# PressSensor2.net
KiCad netlist of a schematic drawn in Altium Designer
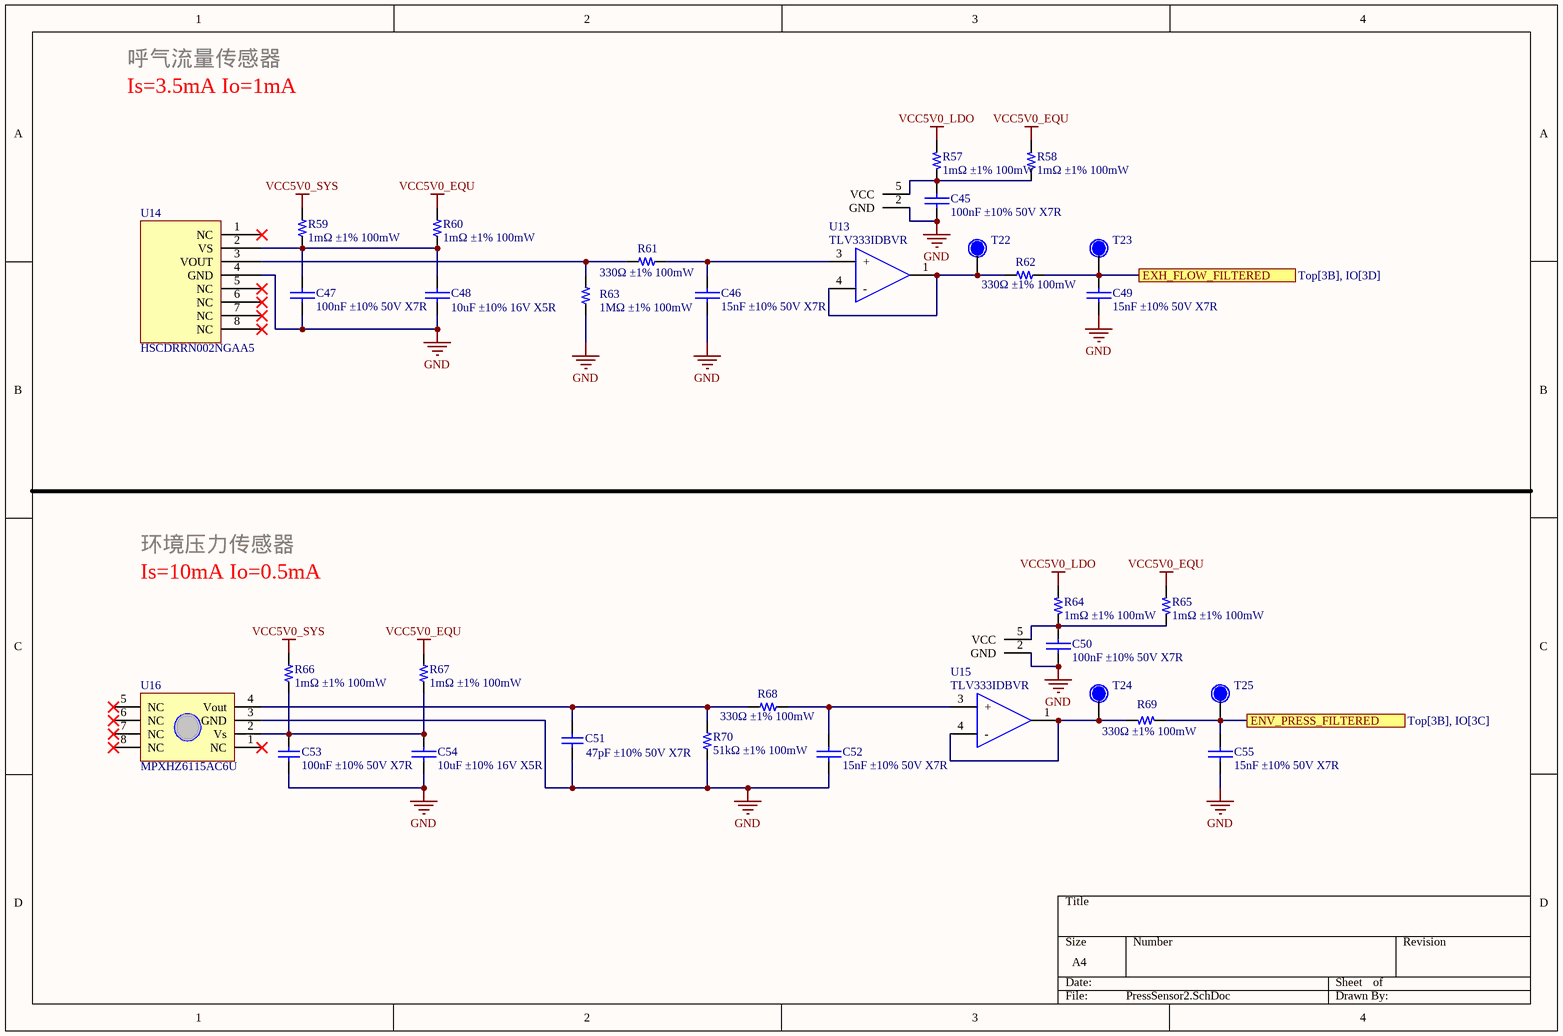
[diagram p0: PressSensor2.SchDoc]

(export (version "E")
  (design (tool "Eeschema 10.0.6"))
  (components
    (comp (ref "C45") (value "100nF ±10% 50V X7R") (footprint "C-0603") (libsource (lib "*") (part "CAP")))
    (comp (ref "C46")
      (value "15nF ±10% 50V X7R")
      (footprint "C-0603")
      (description "Capacitor")
      (libsource (lib "*") (part "CAP"))
    )
    (comp (ref "C47") (value "100nF ±10% 50V X7R") (footprint "C-0603") (libsource (lib "*") (part "CAP")))
    (comp (ref "C48")
      (value "10uF ±10% 16V X5R")
      (footprint "C-0805")
      (description "Capacitor")
      (libsource (lib "*") (part "CAP"))
    )
    (comp (ref "C49")
      (value "15nF ±10% 50V X7R")
      (footprint "C-0603")
      (description "Capacitor")
      (libsource (lib "*") (part "CAP"))
    )
    (comp (ref "C50") (value "100nF ±10% 50V X7R") (footprint "C-0603") (libsource (lib "*") (part "CAP")))
    (comp (ref "C51")
      (value "47pF ±10% 50V X7R")
      (footprint "C-0603")
      (description "贴片瓷介电容100nF±5%,0805")
      (libsource (lib "电容") (part "100nF_1"))
    )
    (comp (ref "C52")
      (value "15nF ±10% 50V X7R")
      (footprint "C-0603")
      (description "Capacitor")
      (libsource (lib "*") (part "CAP"))
    )
    (comp (ref "C53")
      (value "100nF ±10% 50V X7R")
      (footprint "C-0603")
      (libsource (lib "电容") (part "100nF_1"))
    )
    (comp (ref "C54")
      (value "10uF ±10% 16V X5R")
      (footprint "C-0805")
      (description "Capacitor")
      (libsource (lib "*") (part "CAP"))
    )
    (comp (ref "C55")
      (value "15nF ±10% 50V X7R")
      (footprint "C-0603")
      (description "Capacitor")
      (libsource (lib "*") (part "CAP"))
    )
    (comp (ref "R57")
      (value "1mΩ ±1% 100mW")
      (footprint "R-0603")
      (description "国巨\r\n1mΩ ±1% 100mW")
      (libsource (lib "电阻") (part "10K_1"))
    )
    (comp (ref "R58")
      (value "1mΩ ±1% 100mW")
      (footprint "R-0603")
      (description "国巨\r\n1mΩ ±1% 100mW")
      (libsource (lib "电阻") (part "10K_1"))
    )
    (comp (ref "R59")
      (value "1mΩ ±1% 100mW")
      (footprint "R-0603")
      (description "国巨\r\n1mΩ ±1% 100mW")
      (libsource (lib "Device") (part "R-0603"))
    )
    (comp (ref "R60")
      (value "1mΩ ±1% 100mW")
      (footprint "R-0603")
      (description "国巨\r\n1mΩ ±1% 100mW")
      (libsource (lib "Device") (part "R-0603"))
    )
    (comp (ref "R61")
      (value "330Ω ±1% 100mW")
      (footprint "R-0603")
      (libsource (lib "Device") (part "R-0603"))
    )
    (comp (ref "R62")
      (value "330Ω ±1% 100mW")
      (footprint "R-0603")
      (libsource (lib "Device") (part "R-0603"))
    )
    (comp (ref "R63") (value "1MΩ ±1% 100mW") (footprint "R-0603") (libsource (lib "Device") (part "R-0603")))
    (comp (ref "R64")
      (value "1mΩ ±1% 100mW")
      (footprint "R-0603")
      (description "国巨\r\n1mΩ ±1% 100mW")
      (libsource (lib "电阻") (part "10K_1"))
    )
    (comp (ref "R65")
      (value "1mΩ ±1% 100mW")
      (footprint "R-0603")
      (description "国巨\r\n1mΩ ±1% 100mW")
      (libsource (lib "电阻") (part "10K_1"))
    )
    (comp (ref "R66")
      (value "1mΩ ±1% 100mW")
      (footprint "R-0603")
      (description "国巨\r\n1mΩ ±1% 100mW")
      (libsource (lib "Device") (part "R-0603"))
    )
    (comp (ref "R67")
      (value "1mΩ ±1% 100mW")
      (footprint "R-0603")
      (description "国巨\r\n1mΩ ±1% 100mW")
      (libsource (lib "Device") (part "R-0603"))
    )
    (comp (ref "R68")
      (value "330Ω ±1% 100mW")
      (footprint "R-0603")
      (libsource (lib "Device") (part "R-0603"))
    )
    (comp (ref "R69")
      (value "330Ω ±1% 100mW")
      (footprint "R-0603")
      (description "国巨RC0805FR-07100R")
      (libsource (lib "电阻") (part "100Ω_1"))
    )
    (comp (ref "R70")
      (value "51kΩ ±1% 100mW")
      (footprint "R-0603")
      (description "国巨RC0805FR-0710K")
      (libsource (lib "电阻") (part "10K_1"))
    )
    (comp (ref "T22")
      (value "Test?")
      (footprint "TestPad_SMD")
      (description "TestPad_SMD")
      (libsource (lib "Component") (part "TestPad_SMD"))
    )
    (comp (ref "T23")
      (value "Test?")
      (footprint "TestPad_SMD")
      (description "TestPad_SMD")
      (libsource (lib "Component") (part "TestPad_SMD"))
    )
    (comp (ref "T24")
      (value "Test?")
      (footprint "TestPad_SMD")
      (description "TestPad_SMD")
      (libsource (lib "Component") (part "TestPad_SMD"))
    )
    (comp (ref "T25")
      (value "Test?")
      (footprint "TestPad_SMD")
      (description "TestPad_SMD")
      (libsource (lib "Component") (part "TestPad_SMD"))
    )
    (comp (ref "U13")
      (value "TLV333IDBVR")
      (footprint "SOT23-5")
      (description "品牌：TI，型号：TLV333IDBVR,SOIC-8,–25°~+85°C,单运放，ROHS")
      (libsource (lib "IC") (part "TLV333IDBVR"))
    )
    (comp (ref "U14")
      (value "HSCDRRN002NGAA5")
      (footprint "SSCDRR")
      (libsource (lib "NBP电源板") (part "SSCMJJ010KDAA5"))
    )
    (comp (ref "U15")
      (value "TLV333IDBVR")
      (footprint "SOT23-5")
      (description "品牌：TI，型号：TLV333IDBVR,SOIC-8,–25°~+85°C,单运放，ROHS")
      (libsource (lib "IC") (part "TLV333IDBVR"))
    )
    (comp (ref "U16")
      (value "MPXHZ6115AC6U")
      (footprint "1317")
      (libsource (lib "余临时库") (part "MPXHZ6115AC6U"))
    )
  )
  (nets
    (net (code "1") (name "/ENV_PRESS_FILTERED") (class "Default")
      (node (ref "C55") (pin "2") (pinfunction "2_2") (pintype "passive"))
      (node (ref "R69") (pin "1") (pinfunction "TOP_1") (pintype "passive"))
      (node (ref "T25") (pin "1") (pinfunction "1_1") (pintype "passive"))
    )
    (net (code "2") (name "/EXH_FLOW_FILTERED") (class "Default")
      (node (ref "C49") (pin "2") (pinfunction "2_2") (pintype "passive"))
      (node (ref "R62") (pin "1") (pinfunction "1_1") (pintype "passive"))
      (node (ref "T23") (pin "1") (pinfunction "1_1") (pintype "passive"))
    )
    (net (code "3") (name "GND") (class "Default")
      (node (ref "C45") (pin "1") (pinfunction "1_1") (pintype "passive"))
      (node (ref "C46") (pin "1") (pinfunction "1_1") (pintype "passive"))
      (node (ref "C47") (pin "1") (pinfunction "1_1") (pintype "passive"))
      (node (ref "C48") (pin "1") (pinfunction "1_1") (pintype "passive"))
      (node (ref "C49") (pin "1") (pinfunction "1_1") (pintype "passive"))
      (node (ref "C50") (pin "2") (pinfunction "2_2") (pintype "passive"))
      (node (ref "C51") (pin "1") (pinfunction "1_1") (pintype "passive"))
      (node (ref "C52") (pin "1") (pinfunction "1_1") (pintype "passive"))
      (node (ref "C53") (pin "2") (pinfunction "2_2") (pintype "passive"))
      (node (ref "C54") (pin "2") (pinfunction "2_2") (pintype "passive"))
      (node (ref "C55") (pin "1") (pinfunction "1_1") (pintype "passive"))
      (node (ref "R63") (pin "2") (pinfunction "2_2") (pintype "passive"))
      (node (ref "R70") (pin "1") (pinfunction "TOP_1") (pintype "passive"))
      (node (ref "U13") (pin "2") (pinfunction "GND_2") (pintype "passive"))
      (node (ref "U14") (pin "4") (pinfunction "GND_4") (pintype "passive"))
      (node (ref "U15") (pin "2") (pinfunction "GND_2") (pintype "passive"))
      (node (ref "U16") (pin "3") (pinfunction "GND_3") (pintype "passive"))
    )
    (net (code "4") (name "Net-(R57-TOP)") (class "Default")
      (node (ref "C45") (pin "2") (pinfunction "2_2") (pintype "passive"))
      (node (ref "R57") (pin "1") (pinfunction "TOP_1") (pintype "passive"))
      (node (ref "R58") (pin "1") (pinfunction "TOP_1") (pintype "passive"))
      (node (ref "U13") (pin "5") (pinfunction "VCC_5") (pintype "passive"))
    )
    (net (code "5") (name "Net-(R64-TOP)") (class "Default")
      (node (ref "C50") (pin "1") (pinfunction "1_1") (pintype "passive"))
      (node (ref "R64") (pin "1") (pinfunction "TOP_1") (pintype "passive"))
      (node (ref "R65") (pin "1") (pinfunction "TOP_1") (pintype "passive"))
      (node (ref "U15") (pin "5") (pinfunction "VCC_5") (pintype "passive"))
    )
    (net (code "6") (name "Net-(R69-BOT)") (class "Default")
      (node (ref "R69") (pin "2") (pinfunction "BOT_2") (pintype "passive"))
      (node (ref "T24") (pin "1") (pinfunction "1_1") (pintype "passive"))
      (node (ref "U15") (pin "1") (pintype "passive"))
      (node (ref "U15") (pin "4") (pinfunction "-_4") (pintype "passive"))
    )
    (net (code "7") (name "Net-(R70-BOT)") (class "Default")
      (node (ref "C51") (pin "2") (pinfunction "2_2") (pintype "passive"))
      (node (ref "R68") (pin "2") (pinfunction "2_2") (pintype "passive"))
      (node (ref "R70") (pin "2") (pinfunction "BOT_2") (pintype "passive"))
      (node (ref "U16") (pin "4") (pinfunction "Vout_4") (pintype "passive"))
    )
    (net (code "8") (name "Net-(U13-+)") (class "Default")
      (node (ref "C46") (pin "2") (pinfunction "2_2") (pintype "passive"))
      (node (ref "R61") (pin "1") (pinfunction "1_1") (pintype "passive"))
      (node (ref "U13") (pin "3") (pinfunction "+_3") (pintype "passive"))
    )
    (net (code "9") (name "Net-(U13--)") (class "Default")
      (node (ref "R62") (pin "2") (pinfunction "2_2") (pintype "passive"))
      (node (ref "T22") (pin "1") (pinfunction "1_1") (pintype "passive"))
      (node (ref "U13") (pin "1") (pintype "passive"))
      (node (ref "U13") (pin "4") (pinfunction "-_4") (pintype "passive"))
    )
    (net (code "10") (name "Net-(U14-VOUT)") (class "Default")
      (node (ref "R61") (pin "2") (pinfunction "2_2") (pintype "passive"))
      (node (ref "R63") (pin "1") (pinfunction "1_1") (pintype "passive"))
      (node (ref "U14") (pin "3") (pinfunction "VOUT_3") (pintype "passive"))
    )
    (net (code "11") (name "Net-(U14-VS)") (class "Default")
      (node (ref "C47") (pin "2") (pinfunction "2_2") (pintype "passive"))
      (node (ref "C48") (pin "2") (pinfunction "2_2") (pintype "passive"))
      (node (ref "R59") (pin "2") (pinfunction "2_2") (pintype "passive"))
      (node (ref "R60") (pin "2") (pinfunction "2_2") (pintype "passive"))
      (node (ref "U14") (pin "2") (pinfunction "VS_2") (pintype "passive"))
    )
    (net (code "12") (name "Net-(U15-+)") (class "Default")
      (node (ref "C52") (pin "2") (pinfunction "2_2") (pintype "passive"))
      (node (ref "R68") (pin "1") (pinfunction "1_1") (pintype "passive"))
      (node (ref "U15") (pin "3") (pinfunction "+_3") (pintype "passive"))
    )
    (net (code "13") (name "Net-(U16-Vs)") (class "Default")
      (node (ref "C53") (pin "1") (pinfunction "1_1") (pintype "passive"))
      (node (ref "C54") (pin "1") (pinfunction "1_1") (pintype "passive"))
      (node (ref "R66") (pin "2") (pinfunction "2_2") (pintype "passive"))
      (node (ref "R67") (pin "2") (pinfunction "2_2") (pintype "passive"))
      (node (ref "U16") (pin "2") (pinfunction "Vs_2") (pintype "passive"))
    )
    (net (code "14") (name "VCC5V0_EQU") (class "Default")
      (node (ref "R58") (pin "2") (pinfunction "BOT_2") (pintype "passive"))
      (node (ref "R60") (pin "1") (pinfunction "1_1") (pintype "passive"))
      (node (ref "R65") (pin "2") (pinfunction "BOT_2") (pintype "passive"))
      (node (ref "R67") (pin "1") (pinfunction "1_1") (pintype "passive"))
    )
    (net (code "15") (name "VCC5V0_LDO") (class "Default")
      (node (ref "R57") (pin "2") (pinfunction "BOT_2") (pintype "passive"))
      (node (ref "R64") (pin "2") (pinfunction "BOT_2") (pintype "passive"))
    )
    (net (code "16") (name "VCC5V0_SYS") (class "Default")
      (node (ref "R59") (pin "1") (pinfunction "1_1") (pintype "passive"))
      (node (ref "R66") (pin "1") (pinfunction "1_1") (pintype "passive"))
    )
    (net (code "17") (name "unconnected-(U14-NC-Pad1)") (class "Default")
      (node (ref "U14") (pin "1") (pinfunction "NC_1") (pintype "passive+no_connect"))
    )
    (net (code "18") (name "unconnected-(U14-NC-Pad5)") (class "Default")
      (node (ref "U14") (pin "5") (pinfunction "NC_5") (pintype "passive+no_connect"))
    )
    (net (code "19") (name "unconnected-(U14-NC-Pad6)") (class "Default")
      (node (ref "U14") (pin "6") (pinfunction "NC_6") (pintype "passive+no_connect"))
    )
    (net (code "20") (name "unconnected-(U14-NC-Pad7)") (class "Default")
      (node (ref "U14") (pin "7") (pinfunction "NC_7") (pintype "passive+no_connect"))
    )
    (net (code "21") (name "unconnected-(U14-NC-Pad8)") (class "Default")
      (node (ref "U14") (pin "8") (pinfunction "NC_8") (pintype "passive+no_connect"))
    )
    (net (code "22") (name "unconnected-(U16-NC-Pad1)") (class "Default")
      (node (ref "U16") (pin "1") (pinfunction "NC_1") (pintype "passive+no_connect"))
    )
    (net (code "23") (name "unconnected-(U16-NC-Pad5)") (class "Default")
      (node (ref "U16") (pin "5") (pinfunction "NC_5") (pintype "passive+no_connect"))
    )
    (net (code "24") (name "unconnected-(U16-NC-Pad6)") (class "Default")
      (node (ref "U16") (pin "6") (pinfunction "NC_6") (pintype "passive+no_connect"))
    )
    (net (code "25") (name "unconnected-(U16-NC-Pad7)") (class "Default")
      (node (ref "U16") (pin "7") (pinfunction "NC_7") (pintype "passive+no_connect"))
    )
    (net (code "26") (name "unconnected-(U16-NC-Pad8)") (class "Default")
      (node (ref "U16") (pin "8") (pinfunction "NC_8") (pintype "passive+no_connect"))
    )
  )
)
